# tcrt_1.net
KiCad netlist of a schematic drawn in Altium Designer
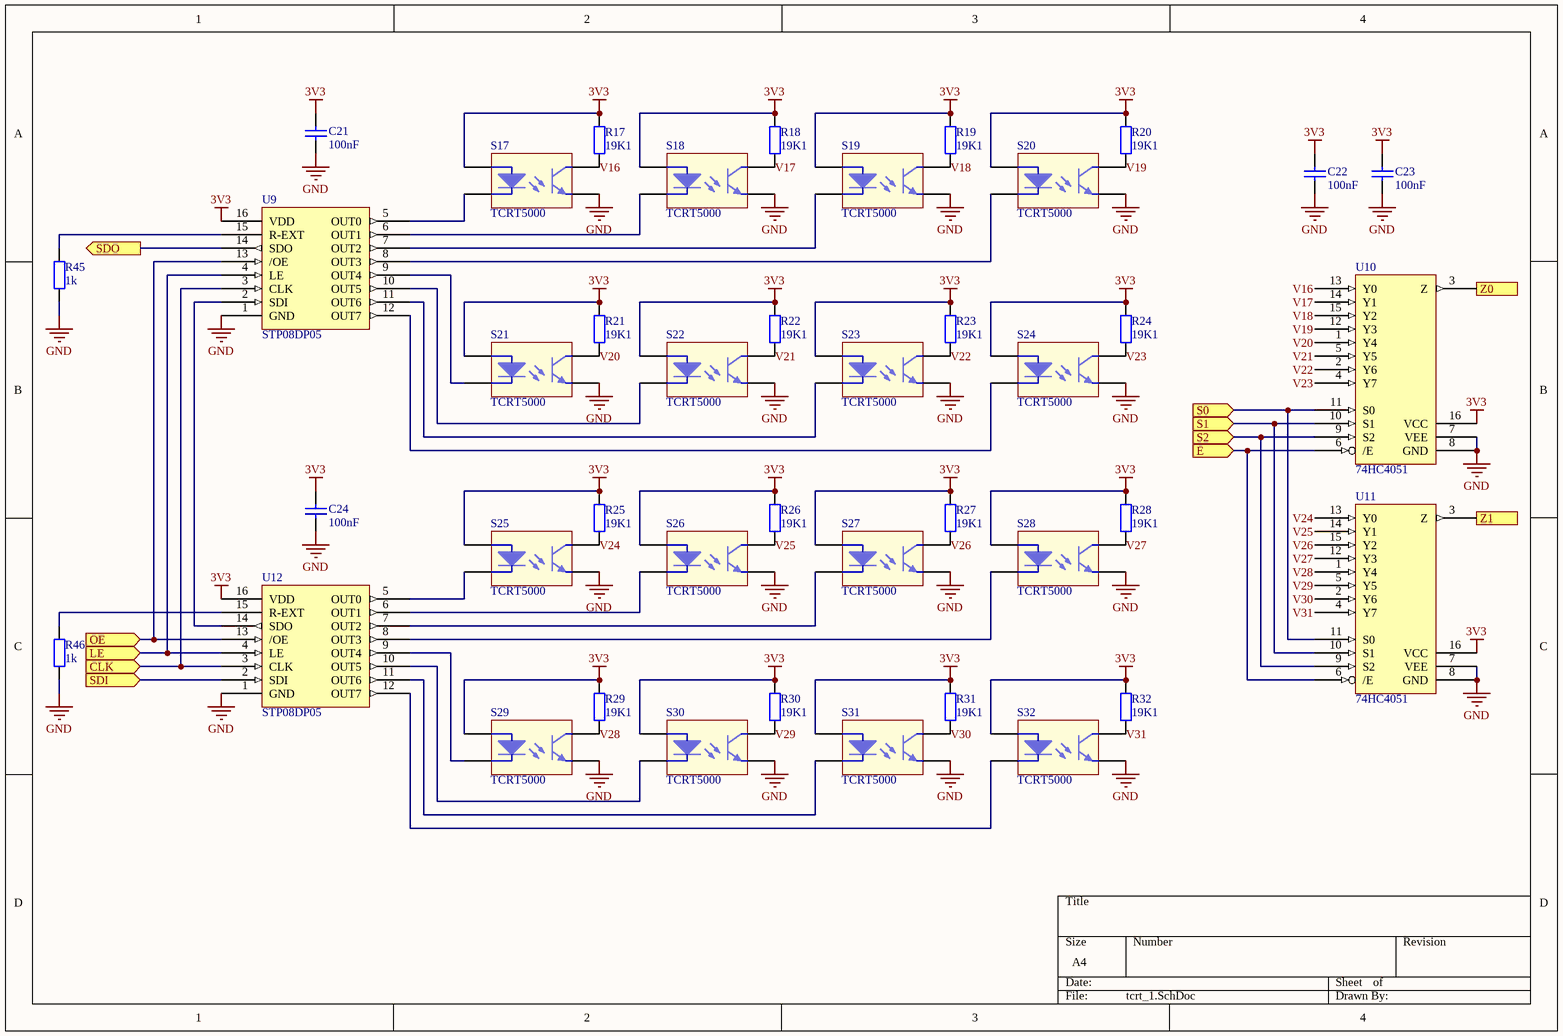
[diagram p0: tcrt_1.SchDoc]

(export (version "E")
  (design (tool "Eeschema 10.0.6"))
  (components
    (comp (ref "C21")
      (value "100nF")
      (footprint "FP_0805_CAP_085")
      (description "Capacitor")
      (libsource (lib "hallglib") (part "CAP"))
    )
    (comp (ref "C22")
      (value "100nF")
      (footprint "FP_0805_CAP_085")
      (description "Capacitor")
      (libsource (lib "hallglib") (part "CAP"))
    )
    (comp (ref "C23")
      (value "100nF")
      (footprint "FP_0805_CAP_085")
      (description "Capacitor")
      (libsource (lib "hallglib") (part "CAP"))
    )
    (comp (ref "C24")
      (value "100nF")
      (footprint "FP_0805_CAP_085")
      (description "Capacitor")
      (libsource (lib "hallglib") (part "CAP"))
    )
    (comp (ref "R17")
      (value "19K1")
      (footprint "FP_0805_RES")
      (description "Resistor")
      (libsource (lib "hallglib") (part "RES"))
    )
    (comp (ref "R18")
      (value "19K1")
      (footprint "FP_0805_RES")
      (description "Resistor")
      (libsource (lib "hallglib") (part "RES"))
    )
    (comp (ref "R19")
      (value "19K1")
      (footprint "FP_0805_RES")
      (description "Resistor")
      (libsource (lib "hallglib") (part "RES"))
    )
    (comp (ref "R20")
      (value "19K1")
      (footprint "FP_0805_RES")
      (description "Resistor")
      (libsource (lib "hallglib") (part "RES"))
    )
    (comp (ref "R21")
      (value "19K1")
      (footprint "FP_0805_RES")
      (description "Resistor")
      (libsource (lib "hallglib") (part "RES"))
    )
    (comp (ref "R22")
      (value "19K1")
      (footprint "FP_0805_RES")
      (description "Resistor")
      (libsource (lib "hallglib") (part "RES"))
    )
    (comp (ref "R23")
      (value "19K1")
      (footprint "FP_0805_RES")
      (description "Resistor")
      (libsource (lib "hallglib") (part "RES"))
    )
    (comp (ref "R24")
      (value "19K1")
      (footprint "FP_0805_RES")
      (description "Resistor")
      (libsource (lib "hallglib") (part "RES"))
    )
    (comp (ref "R25")
      (value "19K1")
      (footprint "FP_0805_RES")
      (description "Resistor")
      (libsource (lib "hallglib") (part "RES"))
    )
    (comp (ref "R26")
      (value "19K1")
      (footprint "FP_0805_RES")
      (description "Resistor")
      (libsource (lib "hallglib") (part "RES"))
    )
    (comp (ref "R27")
      (value "19K1")
      (footprint "FP_0805_RES")
      (description "Resistor")
      (libsource (lib "hallglib") (part "RES"))
    )
    (comp (ref "R28")
      (value "19K1")
      (footprint "FP_0805_RES")
      (description "Resistor")
      (libsource (lib "hallglib") (part "RES"))
    )
    (comp (ref "R29")
      (value "19K1")
      (footprint "FP_0805_RES")
      (description "Resistor")
      (libsource (lib "hallglib") (part "RES"))
    )
    (comp (ref "R30")
      (value "19K1")
      (footprint "FP_0805_RES")
      (description "Resistor")
      (libsource (lib "hallglib") (part "RES"))
    )
    (comp (ref "R31")
      (value "19K1")
      (footprint "FP_0805_RES")
      (description "Resistor")
      (libsource (lib "hallglib") (part "RES"))
    )
    (comp (ref "R32")
      (value "19K1")
      (footprint "FP_0805_RES")
      (description "Resistor")
      (libsource (lib "hallglib") (part "RES"))
    )
    (comp (ref "R45")
      (value "1k")
      (footprint "FP_0805_RES")
      (description "Resistor")
      (libsource (lib "") (part "RES_1"))
    )
    (comp (ref "R46")
      (value "1k")
      (footprint "FP_0805_RES")
      (description "Resistor")
      (libsource (lib "") (part "RES_1"))
    )
    (comp (ref "S17")
      (value "TCRT5000")
      (footprint "TCRT5000_nohole")
      (description "Reflective Optical Sensor")
      (libsource (lib "line-sensor") (part "TCRT5000"))
    )
    (comp (ref "S18")
      (value "TCRT5000")
      (footprint "TCRT5000_nohole")
      (description "Reflective Optical Sensor")
      (libsource (lib "line-sensor") (part "TCRT5000"))
    )
    (comp (ref "S19")
      (value "TCRT5000")
      (footprint "TCRT5000_nohole")
      (description "Reflective Optical Sensor")
      (libsource (lib "line-sensor") (part "TCRT5000"))
    )
    (comp (ref "S20")
      (value "TCRT5000")
      (footprint "TCRT5000_nohole")
      (description "Reflective Optical Sensor")
      (libsource (lib "line-sensor") (part "TCRT5000"))
    )
    (comp (ref "S21")
      (value "TCRT5000")
      (footprint "TCRT5000_nohole")
      (description "Reflective Optical Sensor")
      (libsource (lib "line-sensor") (part "TCRT5000"))
    )
    (comp (ref "S22")
      (value "TCRT5000")
      (footprint "TCRT5000_nohole")
      (description "Reflective Optical Sensor")
      (libsource (lib "line-sensor") (part "TCRT5000"))
    )
    (comp (ref "S23")
      (value "TCRT5000")
      (footprint "TCRT5000_nohole")
      (description "Reflective Optical Sensor")
      (libsource (lib "line-sensor") (part "TCRT5000"))
    )
    (comp (ref "S24")
      (value "TCRT5000")
      (footprint "TCRT5000_nohole")
      (description "Reflective Optical Sensor")
      (libsource (lib "line-sensor") (part "TCRT5000"))
    )
    (comp (ref "S25")
      (value "TCRT5000")
      (footprint "TCRT5000_nohole")
      (description "Reflective Optical Sensor")
      (libsource (lib "line-sensor") (part "TCRT5000"))
    )
    (comp (ref "S26")
      (value "TCRT5000")
      (footprint "TCRT5000_nohole")
      (description "Reflective Optical Sensor")
      (libsource (lib "line-sensor") (part "TCRT5000"))
    )
    (comp (ref "S27")
      (value "TCRT5000")
      (footprint "TCRT5000_nohole")
      (description "Reflective Optical Sensor")
      (libsource (lib "line-sensor") (part "TCRT5000"))
    )
    (comp (ref "S28")
      (value "TCRT5000")
      (footprint "TCRT5000_nohole")
      (description "Reflective Optical Sensor")
      (libsource (lib "line-sensor") (part "TCRT5000"))
    )
    (comp (ref "S29")
      (value "TCRT5000")
      (footprint "TCRT5000_nohole")
      (description "Reflective Optical Sensor")
      (libsource (lib "line-sensor") (part "TCRT5000"))
    )
    (comp (ref "S30")
      (value "TCRT5000")
      (footprint "TCRT5000_nohole")
      (description "Reflective Optical Sensor")
      (libsource (lib "line-sensor") (part "TCRT5000"))
    )
    (comp (ref "S31")
      (value "TCRT5000")
      (footprint "TCRT5000_nohole")
      (description "Reflective Optical Sensor")
      (libsource (lib "line-sensor") (part "TCRT5000"))
    )
    (comp (ref "S32")
      (value "TCRT5000")
      (footprint "TCRT5000_nohole")
      (description "Reflective Optical Sensor")
      (libsource (lib "line-sensor") (part "TCRT5000"))
    )
    (comp (ref "U9")
      (value "STP08DP05")
      (footprint "TSSOP16_2")
      (description "LED driver [8]")
      (libsource (lib "line-sensor") (part "STP08DP05"))
    )
    (comp (ref "U10")
      (value "74HC4051")
      (footprint "TSSOP16_2")
      (description "Analog multiplexer")
      (libsource (lib "line-sensor") (part "74HC4051"))
    )
    (comp (ref "U11")
      (value "74HC4051")
      (footprint "TSSOP16_2")
      (description "Analog multiplexer")
      (libsource (lib "line-sensor") (part "74HC4051"))
    )
    (comp (ref "U12")
      (value "STP08DP05")
      (footprint "TSSOP16_2")
      (description "LED driver [8]")
      (libsource (lib "line-sensor") (part "STP08DP05"))
    )
  )
  (nets
    (net (code "1") (name "/CLK") (class "Default")
      (node (ref "U12") (pin "3") (pinfunction "CLK_3") (pintype "input"))
      (node (ref "U9") (pin "3") (pinfunction "CLK_3") (pintype "input"))
    )
    (net (code "2") (name "/E") (class "Default")
      (node (ref "U10") (pin "6") (pinfunction "/E_6") (pintype "input"))
      (node (ref "U11") (pin "6") (pinfunction "/E_6") (pintype "input"))
    )
    (net (code "3") (name "/LE") (class "Default")
      (node (ref "U12") (pin "4") (pinfunction "LE_4") (pintype "input"))
      (node (ref "U9") (pin "4") (pinfunction "LE_4") (pintype "input"))
    )
    (net (code "4") (name "/OE") (class "Default")
      (node (ref "U12") (pin "13") (pinfunction "/OE_13") (pintype "input"))
      (node (ref "U9") (pin "13") (pinfunction "/OE_13") (pintype "input"))
    )
    (net (code "5") (name "/S0") (class "Default")
      (node (ref "U10") (pin "11") (pinfunction "S0_11") (pintype "input"))
      (node (ref "U11") (pin "11") (pinfunction "S0_11") (pintype "input"))
    )
    (net (code "6") (name "/S1") (class "Default")
      (node (ref "U10") (pin "10") (pinfunction "S1_10") (pintype "input"))
      (node (ref "U11") (pin "10") (pinfunction "S1_10") (pintype "input"))
    )
    (net (code "7") (name "/S2") (class "Default")
      (node (ref "U10") (pin "9") (pinfunction "S2_9") (pintype "input"))
      (node (ref "U11") (pin "9") (pinfunction "S2_9") (pintype "input"))
    )
    (net (code "8") (name "/SDI") (class "Default")
      (node (ref "U12") (pin "2") (pinfunction "SDI_2") (pintype "input"))
    )
    (net (code "9") (name "/SDO") (class "Default")
      (node (ref "U9") (pin "14") (pinfunction "SDO_14") (pintype "output"))
    )
    (net (code "10") (name "/V16") (class "Default")
      (node (ref "R17") (pin "1") (pinfunction "1_1") (pintype "passive"))
      (node (ref "S17") (pin "Coll") (pinfunction "C_Coll") (pintype "passive"))
      (node (ref "U10") (pin "13") (pinfunction "Y0_13") (pintype "input"))
    )
    (net (code "11") (name "/V17") (class "Default")
      (node (ref "R18") (pin "1") (pinfunction "1_1") (pintype "passive"))
      (node (ref "S18") (pin "Coll") (pinfunction "C_Coll") (pintype "passive"))
      (node (ref "U10") (pin "14") (pinfunction "Y1_14") (pintype "input"))
    )
    (net (code "12") (name "/V18") (class "Default")
      (node (ref "R19") (pin "1") (pinfunction "1_1") (pintype "passive"))
      (node (ref "S19") (pin "Coll") (pinfunction "C_Coll") (pintype "passive"))
      (node (ref "U10") (pin "15") (pinfunction "Y2_15") (pintype "input"))
    )
    (net (code "13") (name "/V19") (class "Default")
      (node (ref "R20") (pin "1") (pinfunction "1_1") (pintype "passive"))
      (node (ref "S20") (pin "Coll") (pinfunction "C_Coll") (pintype "passive"))
      (node (ref "U10") (pin "12") (pinfunction "Y3_12") (pintype "input"))
    )
    (net (code "14") (name "/V20") (class "Default")
      (node (ref "R21") (pin "1") (pinfunction "1_1") (pintype "passive"))
      (node (ref "S21") (pin "Coll") (pinfunction "C_Coll") (pintype "passive"))
      (node (ref "U10") (pin "1") (pinfunction "Y4_1") (pintype "input"))
    )
    (net (code "15") (name "/V21") (class "Default")
      (node (ref "R22") (pin "1") (pinfunction "1_1") (pintype "passive"))
      (node (ref "S22") (pin "Coll") (pinfunction "C_Coll") (pintype "passive"))
      (node (ref "U10") (pin "5") (pinfunction "Y5_5") (pintype "input"))
    )
    (net (code "16") (name "/V22") (class "Default")
      (node (ref "R23") (pin "1") (pinfunction "1_1") (pintype "passive"))
      (node (ref "S23") (pin "Coll") (pinfunction "C_Coll") (pintype "passive"))
      (node (ref "U10") (pin "2") (pinfunction "Y6_2") (pintype "input"))
    )
    (net (code "17") (name "/V23") (class "Default")
      (node (ref "R24") (pin "1") (pinfunction "1_1") (pintype "passive"))
      (node (ref "S24") (pin "Coll") (pinfunction "C_Coll") (pintype "passive"))
      (node (ref "U10") (pin "4") (pinfunction "Y7_4") (pintype "input"))
    )
    (net (code "18") (name "/V24") (class "Default")
      (node (ref "R25") (pin "1") (pinfunction "1_1") (pintype "passive"))
      (node (ref "S25") (pin "Coll") (pinfunction "C_Coll") (pintype "passive"))
      (node (ref "U11") (pin "13") (pinfunction "Y0_13") (pintype "input"))
    )
    (net (code "19") (name "/V25") (class "Default")
      (node (ref "R26") (pin "1") (pinfunction "1_1") (pintype "passive"))
      (node (ref "S26") (pin "Coll") (pinfunction "C_Coll") (pintype "passive"))
      (node (ref "U11") (pin "14") (pinfunction "Y1_14") (pintype "input"))
    )
    (net (code "20") (name "/V26") (class "Default")
      (node (ref "R27") (pin "1") (pinfunction "1_1") (pintype "passive"))
      (node (ref "S27") (pin "Coll") (pinfunction "C_Coll") (pintype "passive"))
      (node (ref "U11") (pin "15") (pinfunction "Y2_15") (pintype "input"))
    )
    (net (code "21") (name "/V27") (class "Default")
      (node (ref "R28") (pin "1") (pinfunction "1_1") (pintype "passive"))
      (node (ref "S28") (pin "Coll") (pinfunction "C_Coll") (pintype "passive"))
      (node (ref "U11") (pin "12") (pinfunction "Y3_12") (pintype "input"))
    )
    (net (code "22") (name "/V28") (class "Default")
      (node (ref "R29") (pin "1") (pinfunction "1_1") (pintype "passive"))
      (node (ref "S29") (pin "Coll") (pinfunction "C_Coll") (pintype "passive"))
      (node (ref "U11") (pin "1") (pinfunction "Y4_1") (pintype "input"))
    )
    (net (code "23") (name "/V29") (class "Default")
      (node (ref "R30") (pin "1") (pinfunction "1_1") (pintype "passive"))
      (node (ref "S30") (pin "Coll") (pinfunction "C_Coll") (pintype "passive"))
      (node (ref "U11") (pin "5") (pinfunction "Y5_5") (pintype "input"))
    )
    (net (code "24") (name "/V30") (class "Default")
      (node (ref "R31") (pin "1") (pinfunction "1_1") (pintype "passive"))
      (node (ref "S31") (pin "Coll") (pinfunction "C_Coll") (pintype "passive"))
      (node (ref "U11") (pin "2") (pinfunction "Y6_2") (pintype "input"))
    )
    (net (code "25") (name "/V31") (class "Default")
      (node (ref "R32") (pin "1") (pinfunction "1_1") (pintype "passive"))
      (node (ref "S32") (pin "Coll") (pinfunction "C_Coll") (pintype "passive"))
      (node (ref "U11") (pin "4") (pinfunction "Y7_4") (pintype "input"))
    )
    (net (code "26") (name "/Z0") (class "Default")
      (node (ref "U10") (pin "3") (pinfunction "Z_3") (pintype "output"))
    )
    (net (code "27") (name "/Z1") (class "Default")
      (node (ref "U11") (pin "3") (pinfunction "Z_3") (pintype "output"))
    )
    (net (code "28") (name "3V3") (class "Default")
      (node (ref "C21") (pin "2") (pinfunction "2_2") (pintype "passive"))
      (node (ref "C22") (pin "2") (pinfunction "2_2") (pintype "passive"))
      (node (ref "C23") (pin "2") (pinfunction "2_2") (pintype "passive"))
      (node (ref "C24") (pin "2") (pinfunction "2_2") (pintype "passive"))
      (node (ref "R17") (pin "2") (pinfunction "2_2") (pintype "passive"))
      (node (ref "R18") (pin "2") (pinfunction "2_2") (pintype "passive"))
      (node (ref "R19") (pin "2") (pinfunction "2_2") (pintype "passive"))
      (node (ref "R20") (pin "2") (pinfunction "2_2") (pintype "passive"))
      (node (ref "R21") (pin "2") (pinfunction "2_2") (pintype "passive"))
      (node (ref "R22") (pin "2") (pinfunction "2_2") (pintype "passive"))
      (node (ref "R23") (pin "2") (pinfunction "2_2") (pintype "passive"))
      (node (ref "R24") (pin "2") (pinfunction "2_2") (pintype "passive"))
      (node (ref "R25") (pin "2") (pinfunction "2_2") (pintype "passive"))
      (node (ref "R26") (pin "2") (pinfunction "2_2") (pintype "passive"))
      (node (ref "R27") (pin "2") (pinfunction "2_2") (pintype "passive"))
      (node (ref "R28") (pin "2") (pinfunction "2_2") (pintype "passive"))
      (node (ref "R29") (pin "2") (pinfunction "2_2") (pintype "passive"))
      (node (ref "R30") (pin "2") (pinfunction "2_2") (pintype "passive"))
      (node (ref "R31") (pin "2") (pinfunction "2_2") (pintype "passive"))
      (node (ref "R32") (pin "2") (pinfunction "2_2") (pintype "passive"))
      (node (ref "S17") (pin "A") (pinfunction "A_A") (pintype "passive"))
      (node (ref "S18") (pin "A") (pinfunction "A_A") (pintype "passive"))
      (node (ref "S19") (pin "A") (pinfunction "A_A") (pintype "passive"))
      (node (ref "S20") (pin "A") (pinfunction "A_A") (pintype "passive"))
      (node (ref "S21") (pin "A") (pinfunction "A_A") (pintype "passive"))
      (node (ref "S22") (pin "A") (pinfunction "A_A") (pintype "passive"))
      (node (ref "S23") (pin "A") (pinfunction "A_A") (pintype "passive"))
      (node (ref "S24") (pin "A") (pinfunction "A_A") (pintype "passive"))
      (node (ref "S25") (pin "A") (pinfunction "A_A") (pintype "passive"))
      (node (ref "S26") (pin "A") (pinfunction "A_A") (pintype "passive"))
      (node (ref "S27") (pin "A") (pinfunction "A_A") (pintype "passive"))
      (node (ref "S28") (pin "A") (pinfunction "A_A") (pintype "passive"))
      (node (ref "S29") (pin "A") (pinfunction "A_A") (pintype "passive"))
      (node (ref "S30") (pin "A") (pinfunction "A_A") (pintype "passive"))
      (node (ref "S31") (pin "A") (pinfunction "A_A") (pintype "passive"))
      (node (ref "S32") (pin "A") (pinfunction "A_A") (pintype "passive"))
      (node (ref "U10") (pin "16") (pinfunction "VCC_16") (pintype "power_in"))
      (node (ref "U11") (pin "16") (pinfunction "VCC_16") (pintype "power_in"))
      (node (ref "U12") (pin "16") (pinfunction "VDD_16") (pintype "passive"))
      (node (ref "U9") (pin "16") (pinfunction "VDD_16") (pintype "passive"))
    )
    (net (code "29") (name "GND") (class "Default")
      (node (ref "C21") (pin "1") (pinfunction "1_1") (pintype "passive"))
      (node (ref "C22") (pin "1") (pinfunction "1_1") (pintype "passive"))
      (node (ref "C23") (pin "1") (pinfunction "1_1") (pintype "passive"))
      (node (ref "C24") (pin "1") (pinfunction "1_1") (pintype "passive"))
      (node (ref "R45") (pin "2") (pinfunction "2_2") (pintype "passive"))
      (node (ref "R46") (pin "2") (pinfunction "2_2") (pintype "passive"))
      (node (ref "S17") (pin "E") (pinfunction "E_E") (pintype "passive"))
      (node (ref "S18") (pin "E") (pinfunction "E_E") (pintype "passive"))
      (node (ref "S19") (pin "E") (pinfunction "E_E") (pintype "passive"))
      (node (ref "S20") (pin "E") (pinfunction "E_E") (pintype "passive"))
      (node (ref "S21") (pin "E") (pinfunction "E_E") (pintype "passive"))
      (node (ref "S22") (pin "E") (pinfunction "E_E") (pintype "passive"))
      (node (ref "S23") (pin "E") (pinfunction "E_E") (pintype "passive"))
      (node (ref "S24") (pin "E") (pinfunction "E_E") (pintype "passive"))
      (node (ref "S25") (pin "E") (pinfunction "E_E") (pintype "passive"))
      (node (ref "S26") (pin "E") (pinfunction "E_E") (pintype "passive"))
      (node (ref "S27") (pin "E") (pinfunction "E_E") (pintype "passive"))
      (node (ref "S28") (pin "E") (pinfunction "E_E") (pintype "passive"))
      (node (ref "S29") (pin "E") (pinfunction "E_E") (pintype "passive"))
      (node (ref "S30") (pin "E") (pinfunction "E_E") (pintype "passive"))
      (node (ref "S31") (pin "E") (pinfunction "E_E") (pintype "passive"))
      (node (ref "S32") (pin "E") (pinfunction "E_E") (pintype "passive"))
      (node (ref "U10") (pin "7") (pinfunction "VEE_7") (pintype "power_in"))
      (node (ref "U10") (pin "8") (pinfunction "GND_8") (pintype "power_in"))
      (node (ref "U11") (pin "7") (pinfunction "VEE_7") (pintype "power_in"))
      (node (ref "U11") (pin "8") (pinfunction "GND_8") (pintype "power_in"))
      (node (ref "U12") (pin "1") (pinfunction "GND_1") (pintype "power_in"))
      (node (ref "U9") (pin "1") (pinfunction "GND_1") (pintype "power_in"))
    )
    (net (code "30") (name "Net-(S17-K)") (class "Default")
      (node (ref "S17") (pin "Cath") (pinfunction "K_Cath") (pintype "passive"))
      (node (ref "U9") (pin "5") (pinfunction "OUT0_5") (pintype "output"))
    )
    (net (code "31") (name "Net-(S18-K)") (class "Default")
      (node (ref "S18") (pin "Cath") (pinfunction "K_Cath") (pintype "passive"))
      (node (ref "U9") (pin "6") (pinfunction "OUT1_6") (pintype "output"))
    )
    (net (code "32") (name "Net-(S19-K)") (class "Default")
      (node (ref "S19") (pin "Cath") (pinfunction "K_Cath") (pintype "passive"))
      (node (ref "U9") (pin "7") (pinfunction "OUT2_7") (pintype "output"))
    )
    (net (code "33") (name "Net-(S20-K)") (class "Default")
      (node (ref "S20") (pin "Cath") (pinfunction "K_Cath") (pintype "passive"))
      (node (ref "U9") (pin "8") (pinfunction "OUT3_8") (pintype "output"))
    )
    (net (code "34") (name "Net-(S21-K)") (class "Default")
      (node (ref "S21") (pin "Cath") (pinfunction "K_Cath") (pintype "passive"))
      (node (ref "U9") (pin "9") (pinfunction "OUT4_9") (pintype "output"))
    )
    (net (code "35") (name "Net-(S22-K)") (class "Default")
      (node (ref "S22") (pin "Cath") (pinfunction "K_Cath") (pintype "passive"))
      (node (ref "U9") (pin "10") (pinfunction "OUT5_10") (pintype "output"))
    )
    (net (code "36") (name "Net-(S23-K)") (class "Default")
      (node (ref "S23") (pin "Cath") (pinfunction "K_Cath") (pintype "passive"))
      (node (ref "U9") (pin "11") (pinfunction "OUT6_11") (pintype "output"))
    )
    (net (code "37") (name "Net-(S24-K)") (class "Default")
      (node (ref "S24") (pin "Cath") (pinfunction "K_Cath") (pintype "passive"))
      (node (ref "U9") (pin "12") (pinfunction "OUT7_12") (pintype "output"))
    )
    (net (code "38") (name "Net-(S25-K)") (class "Default")
      (node (ref "S25") (pin "Cath") (pinfunction "K_Cath") (pintype "passive"))
      (node (ref "U12") (pin "5") (pinfunction "OUT0_5") (pintype "output"))
    )
    (net (code "39") (name "Net-(S26-K)") (class "Default")
      (node (ref "S26") (pin "Cath") (pinfunction "K_Cath") (pintype "passive"))
      (node (ref "U12") (pin "6") (pinfunction "OUT1_6") (pintype "output"))
    )
    (net (code "40") (name "Net-(S27-K)") (class "Default")
      (node (ref "S27") (pin "Cath") (pinfunction "K_Cath") (pintype "passive"))
      (node (ref "U12") (pin "7") (pinfunction "OUT2_7") (pintype "output"))
    )
    (net (code "41") (name "Net-(S28-K)") (class "Default")
      (node (ref "S28") (pin "Cath") (pinfunction "K_Cath") (pintype "passive"))
      (node (ref "U12") (pin "8") (pinfunction "OUT3_8") (pintype "output"))
    )
    (net (code "42") (name "Net-(S29-K)") (class "Default")
      (node (ref "S29") (pin "Cath") (pinfunction "K_Cath") (pintype "passive"))
      (node (ref "U12") (pin "9") (pinfunction "OUT4_9") (pintype "output"))
    )
    (net (code "43") (name "Net-(S30-K)") (class "Default")
      (node (ref "S30") (pin "Cath") (pinfunction "K_Cath") (pintype "passive"))
      (node (ref "U12") (pin "10") (pinfunction "OUT5_10") (pintype "output"))
    )
    (net (code "44") (name "Net-(S31-K)") (class "Default")
      (node (ref "S31") (pin "Cath") (pinfunction "K_Cath") (pintype "passive"))
      (node (ref "U12") (pin "11") (pinfunction "OUT6_11") (pintype "output"))
    )
    (net (code "45") (name "Net-(S32-K)") (class "Default")
      (node (ref "S32") (pin "Cath") (pinfunction "K_Cath") (pintype "passive"))
      (node (ref "U12") (pin "12") (pinfunction "OUT7_12") (pintype "output"))
    )
    (net (code "46") (name "Net-(U9-R-EXT)") (class "Default")
      (node (ref "R45") (pin "1") (pinfunction "1_1") (pintype "passive"))
      (node (ref "U9") (pin "15") (pinfunction "R-EXT_15") (pintype "passive"))
    )
    (net (code "47") (name "Net-(U12-R-EXT)") (class "Default")
      (node (ref "R46") (pin "1") (pinfunction "1_1") (pintype "passive"))
      (node (ref "U12") (pin "15") (pinfunction "R-EXT_15") (pintype "passive"))
    )
    (net (code "48") (name "Net-(U12-SDO)") (class "Default")
      (node (ref "U12") (pin "14") (pinfunction "SDO_14") (pintype "output"))
      (node (ref "U9") (pin "2") (pinfunction "SDI_2") (pintype "input"))
    )
  )
)
